# VoltageAmplifier.net
KiCad netlist of a schematic drawn in Altium Designer
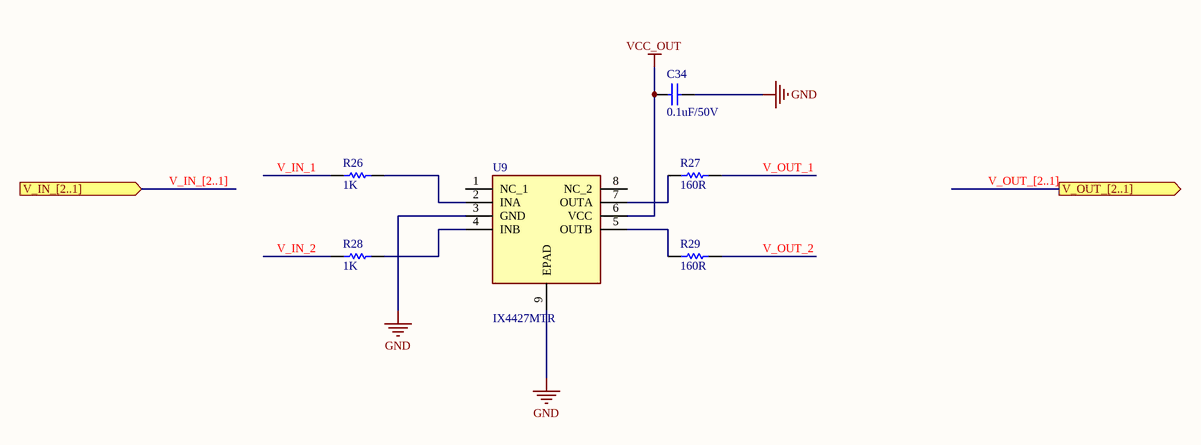
[diagram p0: VoltageAmplifier.SchDoc]

(export (version "E")
  (design (tool "Eeschema 10.0.6"))
  (components
    (comp (ref "C34")
      (value "0.1uF/50V")
      (footprint "0603C")
      (description "Multilayer Ceramic Capacitors MLCC - SMD/SMT 50V 0.1uF 0603 X7R 20%")
      (fields (field (name "MFR") "KEMET") (field (name "MFR PART NO") "C0603C104M5RACTU"))
      (libsource (lib "Miscellaneous Devices") (part "Cap"))
    )
    (comp (ref "R26")
      (value "1K")
      (footprint "0603R")
      (description "Resistor")
      (fields (field (name "MFR") "Vishay / Dale") (field (name "MFR PART NO") "CRCW06031K00FKEAC"))
      (libsource (lib "Miscellaneous Devices") (part "Res1"))
    )
    (comp (ref "R27")
      (value "160R")
      (footprint "0603R")
      (description "Thick Film Resistors - SMD 1/10watt 160ohms 1%")
      (fields (field (name "MFR") "Vishay / Dale") (field (name "MFR PART NO") "CRCW0603160RFKEA"))
      (libsource (lib "Miscellaneous Devices") (part "Res1"))
    )
    (comp (ref "R28")
      (value "1K")
      (footprint "0603R")
      (description "Resistor")
      (fields (field (name "MFR") "Vishay / Dale") (field (name "MFR PART NO") "CRCW06031K00FKEAC"))
      (libsource (lib "Miscellaneous Devices") (part "Res1"))
    )
    (comp (ref "R29")
      (value "160R")
      (footprint "0603R")
      (description "Thick Film Resistors - SMD 1/10watt 160ohms 1%")
      (fields (field (name "MFR") "Vishay / Dale") (field (name "MFR PART NO") "CRCW0603160RFKEA"))
      (libsource (lib "Miscellaneous Devices") (part "Res1"))
    )
    (comp (ref "U9")
      (value "IX4427MTR")
      (footprint "IX4427MTR")
      (description "Gate Drivers Dual 1.5A Low Side Gate Driver")
      (fields
        (field (name "MFR") "IXYS Integrated Circuits")
        (field (name "STOCKIEST PART NO") "849-IX4427MTR")
      )
      (libsource (lib "*") (part "IX4427MTR"))
    )
  )
  (nets
    (net (code "1") (name "/V_IN_1") (class "Default")
      (node (ref "R26") (pin "1") (pinfunction "1_1") (pintype "passive"))
    )
    (net (code "2") (name "/V_IN_2") (class "Default")
      (node (ref "R28") (pin "1") (pinfunction "1_1") (pintype "passive"))
    )
    (net (code "4") (name "/V_OUT_1") (class "Default")
      (node (ref "R27") (pin "2") (pinfunction "2_2") (pintype "passive"))
    )
    (net (code "5") (name "/V_OUT_2") (class "Default")
      (node (ref "R29") (pin "2") (pinfunction "2_2") (pintype "passive"))
    )
    (net (code "7") (name "GND") (class "Default")
      (node (ref "C34") (pin "2") (pinfunction "2_2") (pintype "passive"))
      (node (ref "U9") (pin "3") (pinfunction "GND_3") (pintype "passive"))
      (node (ref "U9") (pin "9") (pinfunction "EPAD_9") (pintype "passive"))
    )
    (net (code "8") (name "Net-(U9-INA)") (class "Default")
      (node (ref "R26") (pin "2") (pinfunction "2_2") (pintype "passive"))
      (node (ref "U9") (pin "2") (pinfunction "INA_2") (pintype "passive"))
    )
    (net (code "9") (name "Net-(U9-INB)") (class "Default")
      (node (ref "R28") (pin "2") (pinfunction "2_2") (pintype "passive"))
      (node (ref "U9") (pin "4") (pinfunction "INB_4") (pintype "passive"))
    )
    (net (code "10") (name "Net-(U9-OUTA)") (class "Default")
      (node (ref "R27") (pin "1") (pinfunction "1_1") (pintype "passive"))
      (node (ref "U9") (pin "7") (pinfunction "OUTA_7") (pintype "passive"))
    )
    (net (code "11") (name "Net-(U9-OUTB)") (class "Default")
      (node (ref "R29") (pin "1") (pinfunction "1_1") (pintype "passive"))
      (node (ref "U9") (pin "5") (pinfunction "OUTB_5") (pintype "passive"))
    )
    (net (code "12") (name "VCC_OUT") (class "Default")
      (node (ref "C34") (pin "1") (pinfunction "1_1") (pintype "passive"))
      (node (ref "U9") (pin "6") (pinfunction "VCC_6") (pintype "passive"))
    )
    (net (code "13") (name "unconnected-(U9-NC_1-Pad1)") (class "Default")
      (node (ref "U9") (pin "1") (pinfunction "NC_1_1") (pintype "passive"))
    )
    (net (code "14") (name "unconnected-(U9-NC_2-Pad8)") (class "Default")
      (node (ref "U9") (pin "8") (pinfunction "NC_2_8") (pintype "passive"))
    )
  )
)
